# Sheet2.net
KiCad netlist of a schematic drawn in Altium Designer
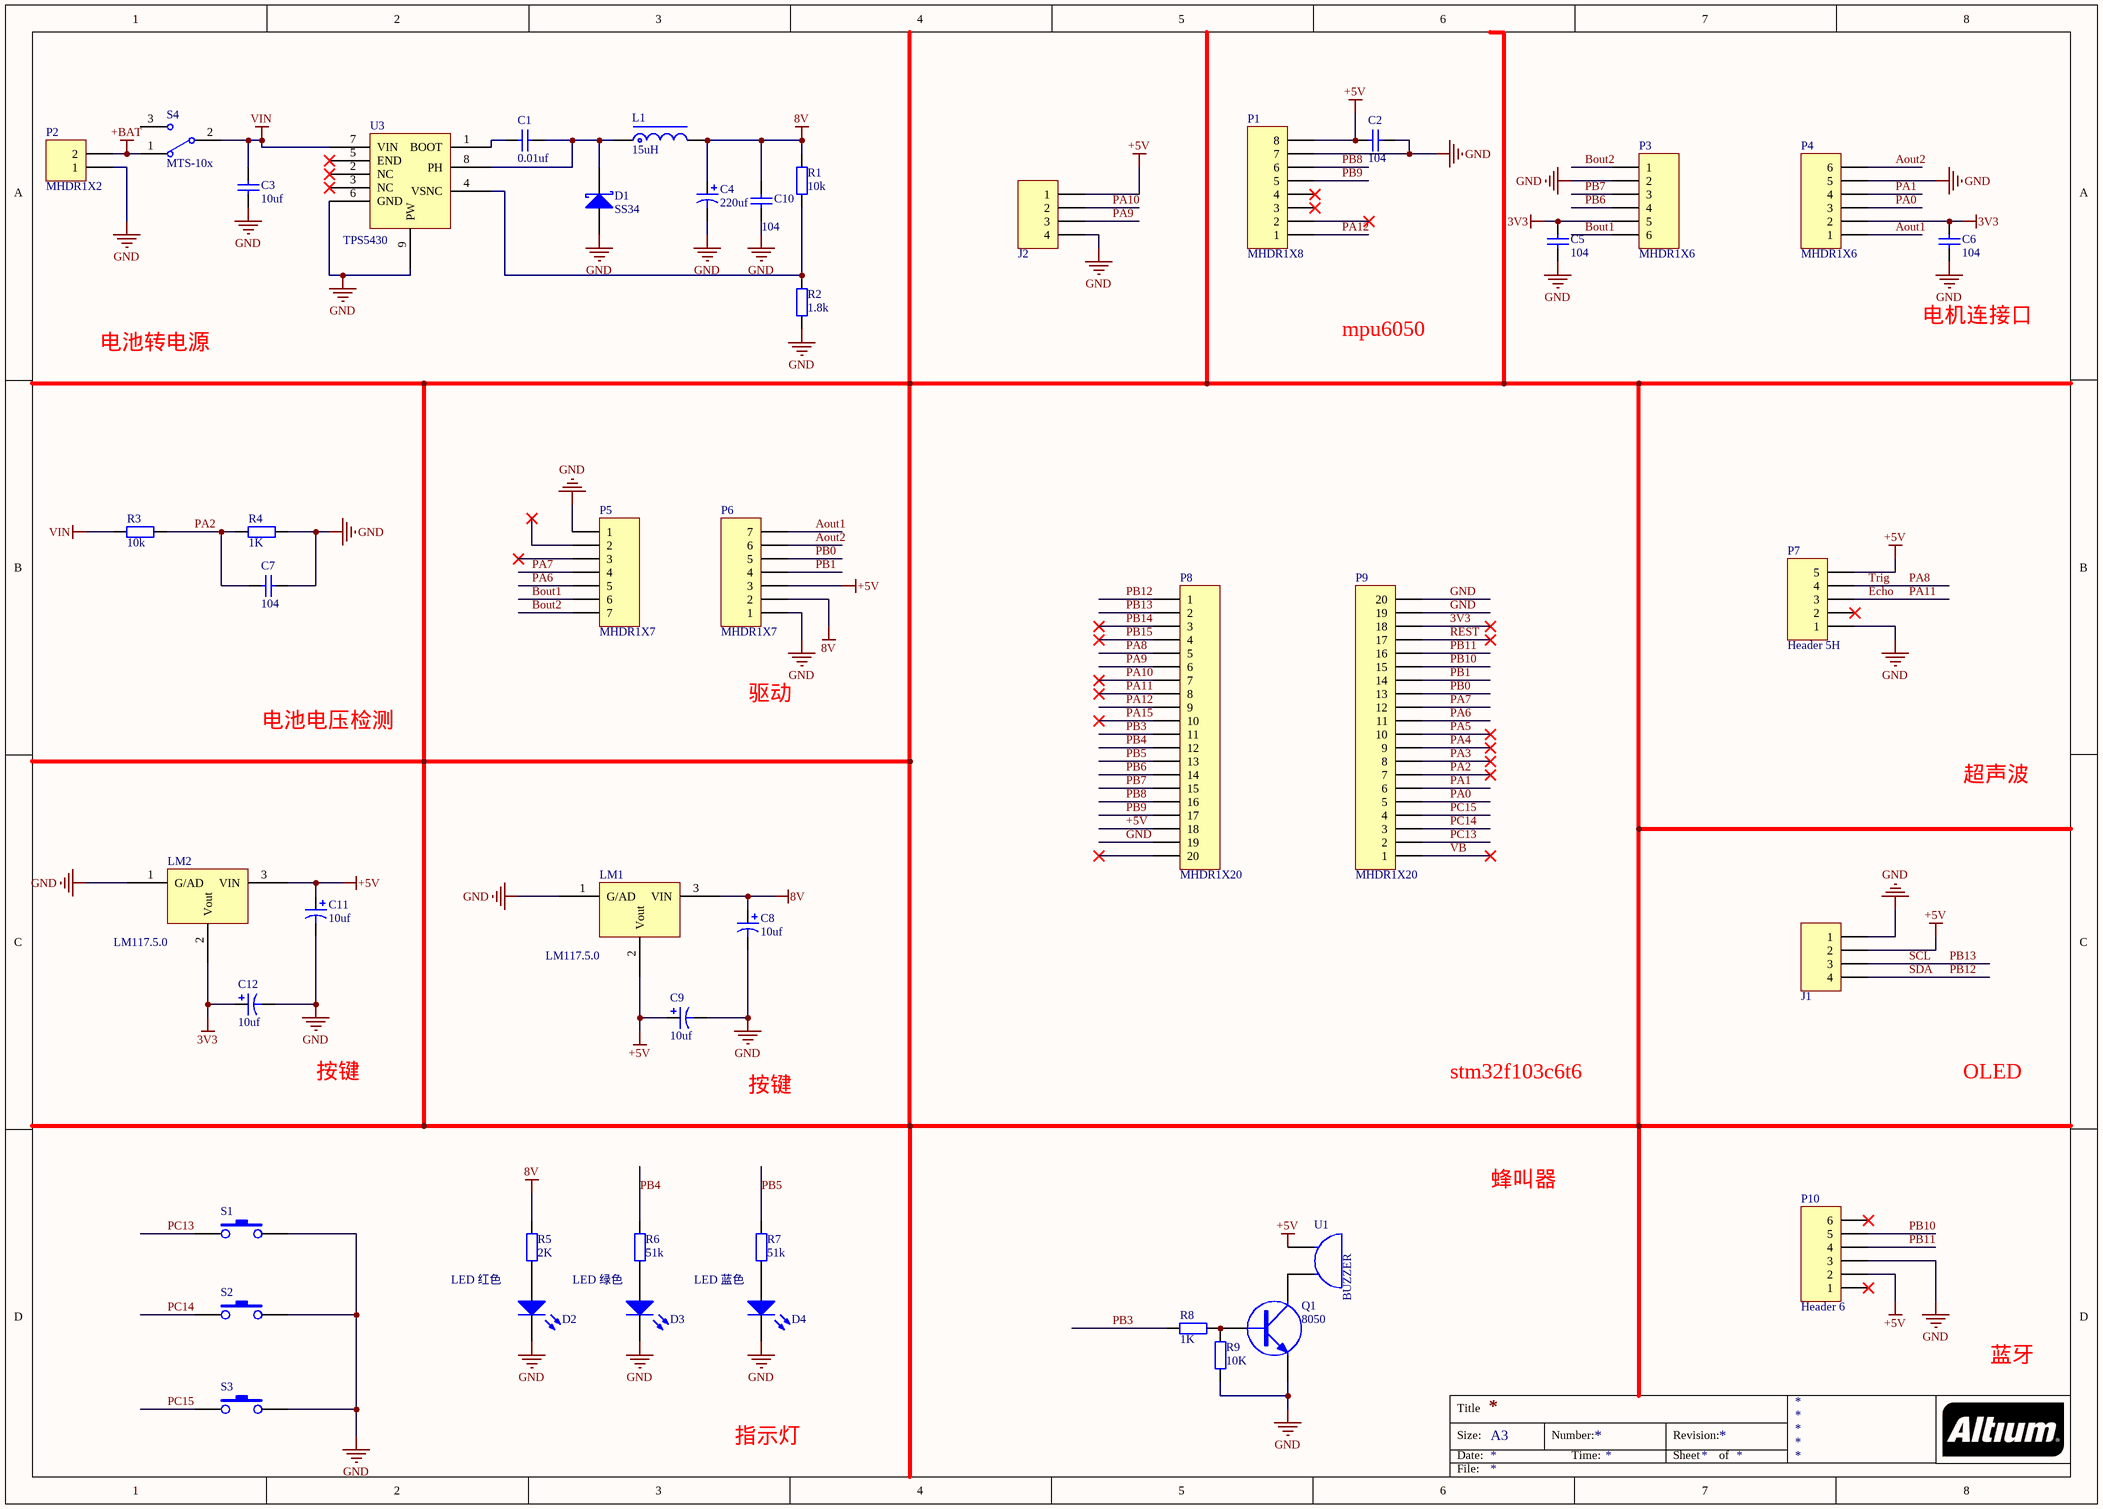
[diagram p0: Sheet2.SchDoc]

(export (version "E")
  (design (tool "Eeschema 10.0.6"))
  (components
    (comp (ref "C1")
      (value "0.01uf")
      (footprint "C0805_L")
      (description "Capacitor (Semiconductor SIM Model)")
      (fields (field (name "PUBLISHER") "Altium Limited"))
      (libsource (lib "Miscellaneous Devices") (part "Cap Semi"))
    )
    (comp (ref "C2")
      (value "104")
      (footprint "C0805_L")
      (description "Capacitor (Semiconductor SIM Model)")
      (fields (field (name "PUBLISHER") "Altium Limited"))
      (libsource (lib "Miscellaneous Devices") (part "Cap Semi"))
    )
    (comp (ref "C3")
      (value "10uf")
      (footprint "C0805_L")
      (description "Capacitor (Semiconductor SIM Model)")
      (fields (field (name "PUBLISHER") "Altium Limited"))
      (libsource (lib "Miscellaneous Devices") (part "Cap Semi"))
    )
    (comp (ref "C4")
      (value "220uf")
      (footprint "CS 6*6 - V")
      (description "Polarized Capacitor (Radial)")
      (fields (field (name "PUBLISHER") "Altium Limited"))
      (libsource (lib "Miscellaneous Devices") (part "Cap Pol1"))
    )
    (comp (ref "C5")
      (value "104")
      (footprint "C0603_L")
      (description "Capacitor (Semiconductor SIM Model)")
      (fields (field (name "PUBLISHER") "Altium Limited"))
      (libsource (lib "Miscellaneous Devices") (part "Cap Semi"))
    )
    (comp (ref "C6")
      (value "104")
      (footprint "C0603_L")
      (description "Capacitor (Semiconductor SIM Model)")
      (fields (field (name "PUBLISHER") "Altium Limited"))
      (libsource (lib "Miscellaneous Devices") (part "Cap Semi"))
    )
    (comp (ref "C7")
      (value "104")
      (footprint "C0603_L")
      (description "Capacitor (Semiconductor SIM Model)")
      (fields (field (name "PUBLISHER") "Altium Limited"))
      (libsource (lib "Miscellaneous Devices") (part "Cap Semi"))
    )
    (comp (ref "C8")
      (value "10uf")
      (footprint "C0805_L")
      (description "Polarized Capacitor (Radial)")
      (fields (field (name "PUBLISHER") "Altium Limited"))
      (libsource (lib "Miscellaneous Devices") (part "Cap Pol1"))
    )
    (comp (ref "C9")
      (value "10uf")
      (footprint "C0805_L")
      (description "Polarized Capacitor (Radial)")
      (fields (field (name "PUBLISHER") "Altium Limited"))
      (libsource (lib "Miscellaneous Devices") (part "Cap Pol1"))
    )
    (comp (ref "C10")
      (value "104")
      (footprint "C0603_L")
      (description "Capacitor (Semiconductor SIM Model)")
      (fields (field (name "PUBLISHER") "Altium Limited"))
      (libsource (lib "Miscellaneous Devices") (part "Cap Semi"))
    )
    (comp (ref "C11")
      (value "10uf")
      (footprint "C0805_L")
      (description "Polarized Capacitor (Radial)")
      (fields (field (name "PUBLISHER") "Altium Limited"))
      (libsource (lib "Miscellaneous Devices") (part "Cap Pol1"))
    )
    (comp (ref "C12")
      (value "10uf")
      (footprint "C0805_L")
      (description "Polarized Capacitor (Radial)")
      (fields (field (name "PUBLISHER") "Altium Limited"))
      (libsource (lib "Miscellaneous Devices") (part "Cap Pol1"))
    )
    (comp (ref "D1")
      (value "SS34")
      (footprint "SMA")
      (description "肖特基二极管")
      (libsource (lib "0.2 - 二极管-TVS-ESD-整流桥") (part "SS34"))
    )
    (comp (ref "D2")
      (value "LED 红色")
      (footprint "LED0603_W")
      (description "发光二极管")
      (libsource (lib "0.3 - LED发光二极管") (part "LED"))
    )
    (comp (ref "D3")
      (value "LED 绿色")
      (footprint "LED0603_W")
      (description "发光二极管")
      (libsource (lib "0.3 - LED发光二极管") (part "LED"))
    )
    (comp (ref "D4")
      (value "LED 蓝色")
      (footprint "LED0603_W")
      (description "发光二极管")
      (libsource (lib "0.3 - LED发光二极管") (part "LED"))
    )
    (comp (ref "J1")
      (value "超声波")
      (footprint "OLED")
      (fields (field (name "PUBLISHER") "Altium Limited"))
      (libsource (lib "平衡小车") (part "Header 4"))
    )
    (comp (ref "J2")
      (value "超声波")
      (footprint "HDR2.54-LI-4P")
      (fields (field (name "PUBLISHER") "Altium Limited"))
      (libsource (lib "平衡小车") (part "Header 4"))
    )
    (comp (ref "L1")
      (value "15uH")
      (footprint "IND-SMD_L12.5-W12.5_RLF12545T")
      (description "贴片功率电感")
      (fields (field (name "版权归属") "源创客"))
      (libsource (lib "3.1   - 电阻-电容-电感") (part "L-CD"))
    )
    (comp (ref "LM1") (value "LM117.5.0") (footprint "SOT-223") (libsource (lib "111") (part "LM117.5.0")))
    (comp (ref "LM2") (value "LM117.5.0") (footprint "SOT-223") (libsource (lib "111") (part "LM117.5.0")))
    (comp (ref "P1")
      (value "MHDR1X8")
      (footprint "HDR2.54-M-LI-8P")
      (description "Header, 8-Pin")
      (fields (field (name "PUBLISHER") "Altium Limited"))
      (libsource (lib "Miscellaneous Connectors") (part "MHDR1X8"))
    )
    (comp (ref "P2")
      (value "MHDR1X2")
      (footprint "KF128-5.08-2P")
      (description "Header, 2-Pin")
      (fields (field (name "PUBLISHER") "Altium Limited"))
      (libsource (lib "Miscellaneous Connectors") (part "MHDR1X2"))
    )
    (comp (ref "P3")
      (value "MHDR1X6")
      (footprint "XH2.54-LI-6P")
      (description "Header, 6-Pin")
      (fields (field (name "PUBLISHER") "Altium Limited"))
      (libsource (lib "Miscellaneous Connectors") (part "MHDR1X6"))
    )
    (comp (ref "P4")
      (value "MHDR1X6")
      (footprint "XH2.54-LI-6P")
      (description "Header, 6-Pin")
      (fields (field (name "PUBLISHER") "Altium Limited"))
      (libsource (lib "") (part "MHDR1X6_1"))
    )
    (comp (ref "P5")
      (value "MHDR1X7")
      (footprint "HDR2.54-M-LI-7P")
      (description "Header, 7-Pin")
      (fields (field (name "PUBLISHER") "Altium Limited"))
      (libsource (lib "") (part "MHDR1X7_1"))
    )
    (comp (ref "P6")
      (value "MHDR1X7")
      (footprint "HDR2.54-M-LI-7P")
      (description "Header, 7-Pin")
      (fields (field (name "PUBLISHER") "Altium Limited"))
      (libsource (lib "Miscellaneous Connectors") (part "MHDR1X7"))
    )
    (comp (ref "P7")
      (value "Header 5H")
      (footprint "HDR2.54-M-LI-5P")
      (description "Header, 5-Pin, Right Angle")
      (fields (field (name "PUBLISHER") "Altium Limited"))
      (libsource (lib "Miscellaneous Connectors") (part "Header 5H"))
    )
    (comp (ref "P8")
      (value "MHDR1X20")
      (footprint "HDR2.54-M-LI-20P")
      (description "Header, 20-Pin")
      (fields (field (name "PUBLISHER") "Altium Limited"))
      (libsource (lib "Miscellaneous Connectors") (part "MHDR1X20"))
    )
    (comp (ref "P9")
      (value "MHDR1X20")
      (footprint "HDR2.54-M-LI-20P")
      (description "Header, 20-Pin")
      (fields (field (name "PUBLISHER") "Altium Limited"))
      (libsource (lib "") (part "MHDR1X20_1"))
    )
    (comp (ref "P10")
      (value "Header 6")
      (footprint "HDR2.54-M-LI-6P")
      (description "Header, 6-Pin")
      (fields (field (name "PUBLISHER") "Altium Limited"))
      (libsource (lib "Miscellaneous Connectors") (part "Header 6"))
    )
    (comp (ref "Q1")
      (value "8050")
      (footprint "SOT23")
      (description "NPN Transistor")
      (libsource (lib "杂元件库") (part "NPN"))
    )
    (comp (ref "R1")
      (value "10k")
      (footprint "R0805_L")
      (description "Resistor")
      (fields (field (name "PUBLISHER") "Altium Limited"))
      (libsource (lib "Miscellaneous Devices") (part "Res2"))
    )
    (comp (ref "R2")
      (value "1.8k")
      (footprint "R0805_L")
      (description "Resistor")
      (fields (field (name "PUBLISHER") "Altium Limited"))
      (libsource (lib "Miscellaneous Devices") (part "Res2"))
    )
    (comp (ref "R3")
      (value "10k")
      (footprint "R0805_L")
      (description "Resistor")
      (fields (field (name "PUBLISHER") "Altium Limited"))
      (libsource (lib "") (part "Res2_1"))
    )
    (comp (ref "R4")
      (value "1K")
      (footprint "R0805_L")
      (description "Resistor")
      (fields (field (name "PUBLISHER") "Altium Limited"))
      (libsource (lib "") (part "Res2_1"))
    )
    (comp (ref "R5")
      (value "2K")
      (footprint "R0805_L")
      (description "Resistor")
      (fields (field (name "PUBLISHER") "Altium Limited"))
      (libsource (lib "Miscellaneous Devices") (part "Res2"))
    )
    (comp (ref "R6")
      (value "51k")
      (footprint "R0805_L")
      (description "Resistor")
      (fields (field (name "PUBLISHER") "Altium Limited"))
      (libsource (lib "Miscellaneous Devices") (part "Res2"))
    )
    (comp (ref "R7")
      (value "51k")
      (footprint "R0805_L")
      (description "Resistor")
      (fields (field (name "PUBLISHER") "Altium Limited"))
      (libsource (lib "Miscellaneous Devices") (part "Res2"))
    )
    (comp (ref "R8")
      (value "1K")
      (footprint "R0805_L")
      (description "Resistor")
      (fields (field (name "Comment") "1k") (field (name "PUBLISHER") "Altium Limited"))
      (libsource (lib "") (part "Res2_1"))
    )
    (comp (ref "R9")
      (value "10K")
      (footprint "R0805_L")
      (description "Resistor")
      (fields (field (name "Comment") "10k") (field (name "PUBLISHER") "Altium Limited"))
      (libsource (lib "Miscellaneous Devices") (part "Res2"))
    )
    (comp (ref "S1") (value "~") (footprint "SW-SMD1") (libsource (lib "开关") (part "微动开关")))
    (comp (ref "S2") (value "~") (footprint "SW-SMD1") (libsource (lib "开关") (part "微动开关")))
    (comp (ref "S3") (value "~") (footprint "SW-SMD1") (libsource (lib "开关") (part "微动开关")))
    (comp (ref "S4")
      (value "MTS-10x")
      (footprint "SW-TH_SS-12D10L9")
      (description "MTS10x系列3脚扭子开关")
      (fields (field (name "版权归属") "源创客"))
      (libsource (lib "5.1   - 按键-开关") (part "MTS-10x"))
    )
    (comp (ref "U1")
      (value "BUZZER")
      (footprint "Buzzer")
      (description "Buzzer")
      (libsource (lib "杂元件库") (part "BUZZER"))
    )
    (comp (ref "U3")
      (value "TPS5430")
      (footprint "SOP-8_L4.9-W3.9-P1.27-LS6.0-BL-EP")
      (libsource (lib "111") (part "TPS5430"))
    )
  )
  (nets
    (net (code "1") (name "+5V") (class "Default")
      (node (ref "C11") (pin "1") (pinfunction "1_1") (pintype "passive"))
      (node (ref "C2") (pin "2") (pinfunction "2_2") (pintype "passive"))
      (node (ref "C9") (pin "1") (pinfunction "1_1") (pintype "passive"))
      (node (ref "J1") (pin "2") (pinfunction "2_2") (pintype "passive"))
      (node (ref "J2") (pin "1") (pinfunction "1_1") (pintype "passive"))
      (node (ref "LM1") (pin "2") (pinfunction "Vout_2") (pintype "passive"))
      (node (ref "LM2") (pin "3") (pinfunction "VIN_3") (pintype "passive"))
      (node (ref "P1") (pin "8") (pinfunction "8_8") (pintype "passive"))
      (node (ref "P10") (pin "2") (pinfunction "2_2") (pintype "passive"))
      (node (ref "P6") (pin "3") (pinfunction "3_3") (pintype "passive"))
      (node (ref "P7") (pin "5") (pinfunction "5_5") (pintype "passive"))
      (node (ref "P8") (pin "18") (pinfunction "18_18") (pintype "passive"))
      (node (ref "U1") (pin "1") (pinfunction "A_1") (pintype "passive"))
    )
    (net (code "2") (name "+BAT") (class "Default")
      (node (ref "P2") (pin "2") (pinfunction "2_2") (pintype "passive"))
      (node (ref "S4") (pin "1") (pinfunction "1_1") (pintype "passive"))
    )
    (net (code "3") (name "/Aout1") (class "Default")
      (node (ref "P4") (pin "1") (pinfunction "1_1") (pintype "passive"))
      (node (ref "P6") (pin "7") (pinfunction "7_7") (pintype "passive"))
    )
    (net (code "4") (name "/Aout2") (class "Default")
      (node (ref "P4") (pin "6") (pinfunction "6_6") (pintype "passive"))
      (node (ref "P6") (pin "6") (pinfunction "6_6") (pintype "passive"))
    )
    (net (code "5") (name "/Bout1") (class "Default")
      (node (ref "P3") (pin "6") (pinfunction "6_6") (pintype "passive"))
      (node (ref "P5") (pin "6") (pinfunction "6_6") (pintype "passive"))
    )
    (net (code "6") (name "/Bout2") (class "Default")
      (node (ref "P3") (pin "1") (pinfunction "1_1") (pintype "passive"))
      (node (ref "P5") (pin "7") (pinfunction "7_7") (pintype "passive"))
    )
    (net (code "7") (name "/Echo") (class "Default")
      (node (ref "P7") (pin "3") (pinfunction "3_3") (pintype "passive"))
      (node (ref "P8") (pin "8") (pinfunction "8_8") (pintype "passive"))
    )
    (net (code "8") (name "/PA0") (class "Default")
      (node (ref "P4") (pin "3") (pinfunction "3_3") (pintype "passive"))
      (node (ref "P9") (pin "5") (pinfunction "5_5") (pintype "passive"))
    )
    (net (code "9") (name "/PA1") (class "Default")
      (node (ref "P4") (pin "4") (pinfunction "4_4") (pintype "passive"))
      (node (ref "P9") (pin "6") (pinfunction "6_6") (pintype "passive"))
    )
    (net (code "10") (name "/PA2") (class "Default")
      (node (ref "C7") (pin "2") (pinfunction "2_2") (pintype "passive"))
      (node (ref "P9") (pin "7") (pinfunction "7_7") (pintype "passive"))
      (node (ref "R3") (pin "2") (pinfunction "2_2") (pintype "passive"))
      (node (ref "R4") (pin "1") (pinfunction "1_1") (pintype "passive"))
    )
    (net (code "11") (name "/PA3") (class "Default")
      (node (ref "P9") (pin "8") (pinfunction "8_8") (pintype "passive+no_connect"))
    )
    (net (code "12") (name "/PA4") (class "Default")
      (node (ref "P9") (pin "9") (pinfunction "9_9") (pintype "passive+no_connect"))
    )
    (net (code "13") (name "/PA5") (class "Default")
      (node (ref "P9") (pin "10") (pinfunction "10_10") (pintype "passive+no_connect"))
    )
    (net (code "14") (name "/PA6") (class "Default")
      (node (ref "P5") (pin "5") (pinfunction "5_5") (pintype "passive"))
      (node (ref "P9") (pin "11") (pinfunction "11_11") (pintype "passive"))
    )
    (net (code "15") (name "/PA7") (class "Default")
      (node (ref "P5") (pin "4") (pinfunction "4_4") (pintype "passive"))
      (node (ref "P9") (pin "12") (pinfunction "12_12") (pintype "passive"))
    )
    (net (code "16") (name "/PA8") (class "Default")
      (node (ref "P7") (pin "4") (pinfunction "4_4") (pintype "passive"))
      (node (ref "P8") (pin "5") (pinfunction "5_5") (pintype "passive"))
    )
    (net (code "17") (name "/PA9") (class "Default")
      (node (ref "J2") (pin "3") (pinfunction "3_3") (pintype "passive"))
      (node (ref "P8") (pin "6") (pinfunction "6_6") (pintype "passive"))
    )
    (net (code "18") (name "/PA10") (class "Default")
      (node (ref "J2") (pin "2") (pinfunction "2_2") (pintype "passive"))
      (node (ref "P8") (pin "7") (pinfunction "7_7") (pintype "passive"))
    )
    (net (code "19") (name "/PA12") (class "Default")
      (node (ref "P1") (pin "1") (pinfunction "1_1") (pintype "passive"))
      (node (ref "P8") (pin "9") (pinfunction "9_9") (pintype "passive"))
    )
    (net (code "20") (name "/PA15") (class "Default")
      (node (ref "P8") (pin "10") (pinfunction "10_10") (pintype "passive+no_connect"))
    )
    (net (code "21") (name "/PB0") (class "Default")
      (node (ref "P6") (pin "5") (pinfunction "5_5") (pintype "passive"))
      (node (ref "P9") (pin "13") (pinfunction "13_13") (pintype "passive"))
    )
    (net (code "22") (name "/PB1") (class "Default")
      (node (ref "P6") (pin "4") (pinfunction "4_4") (pintype "passive"))
      (node (ref "P9") (pin "14") (pinfunction "14_14") (pintype "passive"))
    )
    (net (code "23") (name "/PB3") (class "Default")
      (node (ref "P8") (pin "11") (pinfunction "11_11") (pintype "passive"))
      (node (ref "R8") (pin "1") (pinfunction "1_1") (pintype "passive"))
    )
    (net (code "24") (name "/PB4") (class "Default")
      (node (ref "P8") (pin "12") (pinfunction "12_12") (pintype "passive"))
      (node (ref "R6") (pin "2") (pinfunction "2_2") (pintype "passive"))
    )
    (net (code "25") (name "/PB5") (class "Default")
      (node (ref "P8") (pin "13") (pinfunction "13_13") (pintype "passive"))
      (node (ref "R7") (pin "2") (pinfunction "2_2") (pintype "passive"))
    )
    (net (code "26") (name "/PB6") (class "Default")
      (node (ref "P3") (pin "4") (pinfunction "4_4") (pintype "passive"))
      (node (ref "P8") (pin "14") (pinfunction "14_14") (pintype "passive"))
    )
    (net (code "27") (name "/PB7") (class "Default")
      (node (ref "P3") (pin "3") (pinfunction "3_3") (pintype "passive"))
      (node (ref "P8") (pin "15") (pinfunction "15_15") (pintype "passive"))
    )
    (net (code "28") (name "/PB8") (class "Default")
      (node (ref "P1") (pin "6") (pinfunction "6_6") (pintype "passive"))
      (node (ref "P8") (pin "16") (pinfunction "16_16") (pintype "passive"))
    )
    (net (code "29") (name "/PB9") (class "Default")
      (node (ref "P1") (pin "5") (pinfunction "5_5") (pintype "passive"))
      (node (ref "P8") (pin "17") (pinfunction "17_17") (pintype "passive"))
    )
    (net (code "30") (name "/PB10") (class "Default")
      (node (ref "P10") (pin "5") (pinfunction "5_5") (pintype "passive"))
      (node (ref "P9") (pin "15") (pinfunction "15_15") (pintype "passive"))
    )
    (net (code "31") (name "/PB11") (class "Default")
      (node (ref "P10") (pin "4") (pinfunction "4_4") (pintype "passive"))
      (node (ref "P9") (pin "16") (pinfunction "16_16") (pintype "passive"))
    )
    (net (code "32") (name "/PB12") (class "Default")
      (node (ref "J1") (pin "4") (pinfunction "4_4") (pintype "passive"))
      (node (ref "P8") (pin "1") (pinfunction "1_1") (pintype "passive"))
    )
    (net (code "33") (name "/PB13") (class "Default")
      (node (ref "J1") (pin "3") (pinfunction "3_3") (pintype "passive"))
      (node (ref "P8") (pin "2") (pinfunction "2_2") (pintype "passive"))
    )
    (net (code "34") (name "/PB14") (class "Default")
      (node (ref "P8") (pin "3") (pinfunction "3_3") (pintype "passive+no_connect"))
    )
    (net (code "35") (name "/PB15") (class "Default")
      (node (ref "P8") (pin "4") (pinfunction "4_4") (pintype "passive+no_connect"))
    )
    (net (code "36") (name "/PC13") (class "Default")
      (node (ref "P9") (pin "2") (pinfunction "2_2") (pintype "passive"))
      (node (ref "S1") (pin "1") (pinfunction "1_1") (pintype "passive"))
    )
    (net (code "37") (name "/PC14") (class "Default")
      (node (ref "P9") (pin "3") (pinfunction "3_3") (pintype "passive"))
      (node (ref "S2") (pin "1") (pinfunction "1_1") (pintype "passive"))
    )
    (net (code "38") (name "/PC15") (class "Default")
      (node (ref "P9") (pin "4") (pinfunction "4_4") (pintype "passive"))
      (node (ref "S3") (pin "1") (pinfunction "1_1") (pintype "passive"))
    )
    (net (code "39") (name "/REST") (class "Default")
      (node (ref "P9") (pin "17") (pinfunction "17_17") (pintype "passive+no_connect"))
    )
    (net (code "40") (name "/VB") (class "Default")
      (node (ref "P9") (pin "1") (pinfunction "1_1") (pintype "passive+no_connect"))
    )
    (net (code "41") (name "3V3") (class "Default")
      (node (ref "C12") (pin "1") (pinfunction "1_1") (pintype "passive"))
      (node (ref "C5") (pin "1") (pinfunction "1_1") (pintype "passive"))
      (node (ref "C6") (pin "1") (pinfunction "1_1") (pintype "passive"))
      (node (ref "LM2") (pin "2") (pinfunction "Vout_2") (pintype "passive"))
      (node (ref "P3") (pin "5") (pinfunction "5_5") (pintype "passive"))
      (node (ref "P4") (pin "2") (pinfunction "2_2") (pintype "passive"))
      (node (ref "P9") (pin "18") (pinfunction "18_18") (pintype "passive"))
    )
    (net (code "42") (name "8V") (class "Default")
      (node (ref "C10") (pin "2") (pinfunction "2_2") (pintype "passive"))
      (node (ref "C4") (pin "1") (pinfunction "1_1") (pintype "passive"))
      (node (ref "C8") (pin "1") (pinfunction "1_1") (pintype "passive"))
      (node (ref "L1") (pin "2") (pinfunction "2_2") (pintype "passive"))
      (node (ref "LM1") (pin "3") (pinfunction "VIN_3") (pintype "passive"))
      (node (ref "P6") (pin "2") (pinfunction "2_2") (pintype "passive"))
      (node (ref "R1") (pin "2") (pinfunction "2_2") (pintype "passive"))
      (node (ref "R5") (pin "2") (pinfunction "2_2") (pintype "passive"))
    )
    (net (code "43") (name "GND") (class "Default")
      (node (ref "C10") (pin "1") (pinfunction "1_1") (pintype "passive"))
      (node (ref "C11") (pin "2") (pinfunction "2_2") (pintype "passive"))
      (node (ref "C12") (pin "2") (pinfunction "2_2") (pintype "passive"))
      (node (ref "C2") (pin "1") (pinfunction "1_1") (pintype "passive"))
      (node (ref "C3") (pin "1") (pinfunction "1_1") (pintype "passive"))
      (node (ref "C4") (pin "2") (pinfunction "2_2") (pintype "passive"))
      (node (ref "C5") (pin "2") (pinfunction "2_2") (pintype "passive"))
      (node (ref "C6") (pin "2") (pinfunction "2_2") (pintype "passive"))
      (node (ref "C7") (pin "1") (pinfunction "1_1") (pintype "passive"))
      (node (ref "C8") (pin "2") (pinfunction "2_2") (pintype "passive"))
      (node (ref "C9") (pin "2") (pinfunction "2_2") (pintype "passive"))
      (node (ref "D1") (pin "1") (pinfunction "A_1") (pintype "passive"))
      (node (ref "D2") (pin "2") (pinfunction "K_2") (pintype "passive"))
      (node (ref "D3") (pin "2") (pinfunction "K_2") (pintype "passive"))
      (node (ref "D4") (pin "2") (pinfunction "K_2") (pintype "passive"))
      (node (ref "J1") (pin "1") (pinfunction "1_1") (pintype "passive"))
      (node (ref "J2") (pin "4") (pinfunction "4_4") (pintype "passive"))
      (node (ref "LM1") (pin "1") (pinfunction "G/AD_1") (pintype "passive"))
      (node (ref "LM2") (pin "1") (pinfunction "G/AD_1") (pintype "passive"))
      (node (ref "P1") (pin "7") (pinfunction "7_7") (pintype "passive"))
      (node (ref "P10") (pin "3") (pinfunction "3_3") (pintype "passive"))
      (node (ref "P2") (pin "1") (pinfunction "1_1") (pintype "passive"))
      (node (ref "P3") (pin "2") (pinfunction "2_2") (pintype "passive"))
      (node (ref "P4") (pin "5") (pinfunction "5_5") (pintype "passive"))
      (node (ref "P5") (pin "1") (pinfunction "1_1") (pintype "passive"))
      (node (ref "P6") (pin "1") (pinfunction "1_1") (pintype "passive"))
      (node (ref "P7") (pin "1") (pinfunction "1_1") (pintype "passive"))
      (node (ref "P8") (pin "19") (pinfunction "19_19") (pintype "passive"))
      (node (ref "P9") (pin "19") (pinfunction "19_19") (pintype "passive"))
      (node (ref "P9") (pin "20") (pinfunction "20_20") (pintype "passive"))
      (node (ref "Q1") (pin "2") (pinfunction "E_2") (pintype "passive"))
      (node (ref "R2") (pin "1") (pinfunction "1_1") (pintype "passive"))
      (node (ref "R4") (pin "2") (pinfunction "2_2") (pintype "passive"))
      (node (ref "R9") (pin "1") (pinfunction "1_1") (pintype "passive"))
      (node (ref "S1") (pin "2") (pinfunction "2_2") (pintype "passive"))
      (node (ref "S2") (pin "2") (pinfunction "2_2") (pintype "passive"))
      (node (ref "S3") (pin "2") (pinfunction "2_2") (pintype "passive"))
      (node (ref "U3") (pin "6") (pinfunction "GND_6") (pintype "passive"))
      (node (ref "U3") (pin "9") (pinfunction "PW_9") (pintype "passive"))
    )
    (net (code "44") (name "Net-(D1-K)") (class "Default")
      (node (ref "C1") (pin "1") (pinfunction "1_1") (pintype "passive"))
      (node (ref "D1") (pin "2") (pinfunction "K_2") (pintype "passive"))
      (node (ref "L1") (pin "1") (pinfunction "1_1") (pintype "passive"))
      (node (ref "U3") (pin "8") (pinfunction "PH_8") (pintype "passive"))
    )
    (net (code "45") (name "Net-(D2-A)") (class "Default")
      (node (ref "D2") (pin "1") (pinfunction "A_1") (pintype "passive"))
      (node (ref "R5") (pin "1") (pinfunction "1_1") (pintype "passive"))
    )
    (net (code "46") (name "Net-(D3-A)") (class "Default")
      (node (ref "D3") (pin "1") (pinfunction "A_1") (pintype "passive"))
      (node (ref "R6") (pin "1") (pinfunction "1_1") (pintype "passive"))
    )
    (net (code "47") (name "Net-(D4-A)") (class "Default")
      (node (ref "D4") (pin "1") (pinfunction "A_1") (pintype "passive"))
      (node (ref "R7") (pin "1") (pinfunction "1_1") (pintype "passive"))
    )
    (net (code "48") (name "Net-(Q1-B)") (class "Default")
      (node (ref "Q1") (pin "1") (pinfunction "B_1") (pintype "passive"))
      (node (ref "R8") (pin "2") (pinfunction "2_2") (pintype "passive"))
      (node (ref "R9") (pin "2") (pinfunction "2_2") (pintype "passive"))
    )
    (net (code "49") (name "Net-(Q1-C)") (class "Default")
      (node (ref "Q1") (pin "3") (pinfunction "C_3") (pintype "passive"))
      (node (ref "U1") (pin "2") (pinfunction "B_2") (pintype "passive"))
    )
    (net (code "50") (name "Net-(U3-BOOT)") (class "Default")
      (node (ref "C1") (pin "2") (pinfunction "2_2") (pintype "passive"))
      (node (ref "U3") (pin "1") (pinfunction "BOOT_1") (pintype "passive"))
    )
    (net (code "51") (name "Net-(U3-VSNC)") (class "Default")
      (node (ref "R1") (pin "1") (pinfunction "1_1") (pintype "passive"))
      (node (ref "R2") (pin "2") (pinfunction "2_2") (pintype "passive"))
      (node (ref "U3") (pin "4") (pinfunction "VSNC_4") (pintype "passive"))
    )
    (net (code "52") (name "VIN") (class "Default")
      (node (ref "C3") (pin "2") (pinfunction "2_2") (pintype "passive"))
      (node (ref "R3") (pin "1") (pinfunction "1_1") (pintype "passive"))
      (node (ref "S4") (pin "2") (pinfunction "2_2") (pintype "passive"))
      (node (ref "U3") (pin "7") (pinfunction "VIN_7") (pintype "passive"))
    )
    (net (code "53") (name "unconnected-(P1-Pad2)") (class "Default")
      (node (ref "P1") (pin "2") (pinfunction "2_2") (pintype "passive+no_connect"))
    )
    (net (code "54") (name "unconnected-(P1-Pad3)") (class "Default")
      (node (ref "P1") (pin "3") (pinfunction "3_3") (pintype "passive+no_connect"))
    )
    (net (code "55") (name "unconnected-(P1-Pad4)") (class "Default")
      (node (ref "P1") (pin "4") (pinfunction "4_4") (pintype "passive+no_connect"))
    )
    (net (code "56") (name "unconnected-(P5-Pad2)") (class "Default")
      (node (ref "P5") (pin "2") (pinfunction "2_2") (pintype "passive+no_connect"))
    )
    (net (code "57") (name "unconnected-(P5-Pad3)") (class "Default")
      (node (ref "P5") (pin "3") (pinfunction "3_3") (pintype "passive+no_connect"))
    )
    (net (code "58") (name "unconnected-(P7-Pad2)") (class "Default")
      (node (ref "P7") (pin "2") (pinfunction "2_2") (pintype "passive+no_connect"))
    )
    (net (code "59") (name "unconnected-(P8-Pad20)") (class "Default")
      (node (ref "P8") (pin "20") (pinfunction "20_20") (pintype "passive+no_connect"))
    )
    (net (code "60") (name "unconnected-(P10-Pad1)") (class "Default")
      (node (ref "P10") (pin "1") (pinfunction "1_1") (pintype "passive+no_connect"))
    )
    (net (code "61") (name "unconnected-(P10-Pad6)") (class "Default")
      (node (ref "P10") (pin "6") (pinfunction "6_6") (pintype "passive+no_connect"))
    )
    (net (code "62") (name "unconnected-(S4-Pad3)") (class "Default")
      (node (ref "S4") (pin "3") (pinfunction "3_3") (pintype "passive"))
    )
    (net (code "63") (name "unconnected-(U3-END-Pad5)") (class "Default")
      (node (ref "U3") (pin "5") (pinfunction "END_5") (pintype "passive+no_connect"))
    )
    (net (code "64") (name "unconnected-(U3-NC-Pad2)") (class "Default")
      (node (ref "U3") (pin "2") (pinfunction "NC_2") (pintype "passive+no_connect"))
    )
    (net (code "65") (name "unconnected-(U3-NC-Pad3)") (class "Default")
      (node (ref "U3") (pin "3") (pinfunction "NC_3") (pintype "passive+no_connect"))
    )
  )
)
